# PG01_BLE_Module.net
KiCad netlist of a schematic drawn in Altium Designer
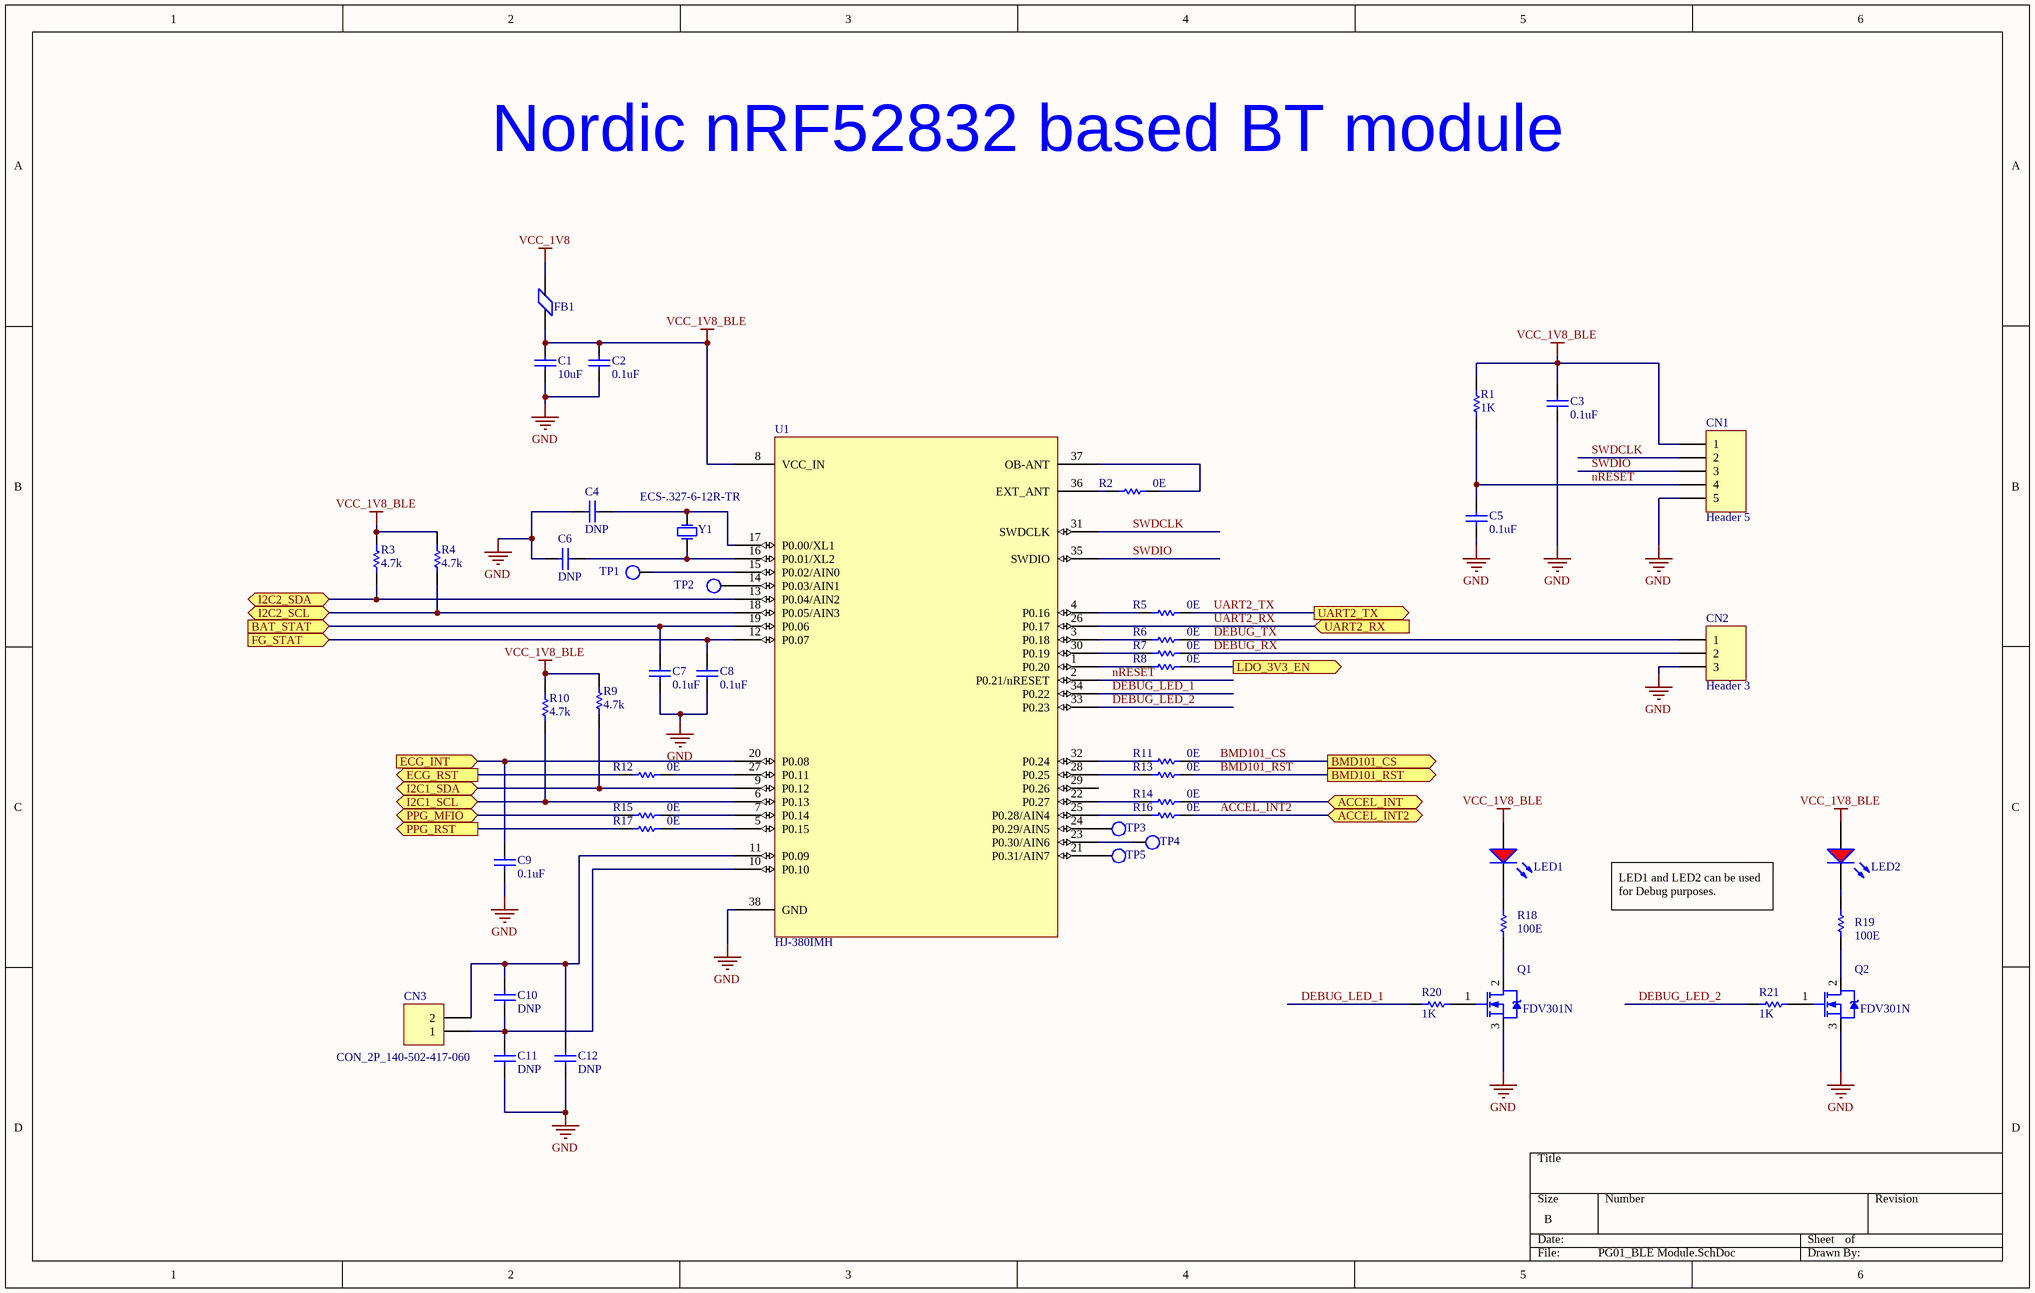
[diagram p0: PG01_BLE Module.SchDoc]

(export (version "E")
  (design (tool "Eeschema 10.0.6"))
  (components
    (comp (ref "C1")
      (value "10uF")
      (footprint "0805C")
      (description "CAP CER 10UF 16V X7R 0805")
      (libsource (lib "Smart Ring Components") (part "CAP_0805_10uF_16V"))
    )
    (comp (ref "C2")
      (value "0.1uF")
      (footprint "0402C")
      (description "CAP CER 0.1UF 50V X7R 0402")
      (libsource (lib "Smart Ring Components") (part "CAP_0402_0.1uF_50V"))
    )
    (comp (ref "C3")
      (value "0.1uF")
      (footprint "0402C")
      (description "CAP CER 0.1UF 50V X7R 0402")
      (libsource (lib "Smart Ring Components") (part "CAP_0402_0.1uF_50V"))
    )
    (comp (ref "C4")
      (value "DNP")
      (footprint "0402C")
      (description "CAP CER DNP 0402")
      (fields (field (name "MFR") "Generic"))
      (libsource (lib "Smart Ring Components") (part "CAP_0402_DNP"))
    )
    (comp (ref "C5")
      (value "0.1uF")
      (footprint "0402C")
      (description "CAP CER 0.1UF 50V X7R 0402")
      (libsource (lib "Smart Ring Components") (part "CAP_0402_0.1uF_50V"))
    )
    (comp (ref "C6")
      (value "DNP")
      (footprint "0402C")
      (description "CAP CER DNP 0402")
      (fields (field (name "MFR") "Generic"))
      (libsource (lib "Smart Ring Components") (part "CAP_0402_DNP"))
    )
    (comp (ref "C7")
      (value "0.1uF")
      (footprint "0402C")
      (description "CAP CER 0.1UF 50V X7R 0402")
      (libsource (lib "Smart Ring Components") (part "CAP_0402_0.1uF_50V"))
    )
    (comp (ref "C8")
      (value "0.1uF")
      (footprint "0402C")
      (description "CAP CER 0.1UF 50V X7R 0402")
      (libsource (lib "Smart Ring Components") (part "CAP_0402_0.1uF_50V"))
    )
    (comp (ref "C9")
      (value "0.1uF")
      (footprint "0402C")
      (description "CAP CER 0.1UF 50V X7R 0402")
      (libsource (lib "Smart Ring Components") (part "CAP_0402_0.1uF_50V"))
    )
    (comp (ref "C10")
      (value "DNP")
      (footprint "0402C")
      (description "CAP CER DNP 0402")
      (fields (field (name "MFR") "Generic"))
      (libsource (lib "Smart Ring Components") (part "CAP_0402_DNP"))
    )
    (comp (ref "C11")
      (value "DNP")
      (footprint "0402C")
      (description "CAP CER DNP 0402")
      (fields (field (name "MFR") "Generic"))
      (libsource (lib "Smart Ring Components") (part "CAP_0402_DNP"))
    )
    (comp (ref "C12")
      (value "DNP")
      (footprint "0402C")
      (description "CAP CER DNP 0402")
      (fields (field (name "MFR") "Generic"))
      (libsource (lib "Smart Ring Components") (part "CAP_0402_DNP"))
    )
    (comp (ref "CN1")
      (value "Header 5")
      (footprint "HDR1X5")
      (description "5 POS 2.00MM(.079) SINGLE ROW SM")
      (fields (field (name "MFR") "Cvilux USA") (field (name "MPN") "CI0105M1HR0-NH"))
      (libsource (lib "Smart Ring Components") (part "CON_5P_CI0105M1HR0-NH"))
    )
    (comp (ref "CN2")
      (value "Header 3")
      (footprint "HDR1X3")
      (description "3 POS 2.00MM(.079) SINGLE ROW SM")
      (fields (field (name "MFR") "Cvilux USA") (field (name "MPN") "CI0103M1HR0-NH"))
      (libsource (lib "Smart Ring Components") (part "CON_3P_CI0103M1HR0-NH"))
    )
    (comp (ref "CN3")
      (value "CON_2P_140-502-417-060")
      (footprint "140-502-417-060")
      (description "2.0MM PITCH CONNECTOR WITH 2 SUR")
      (fields (field (name "MFR") "EDAC Inc.") (field (name "MPN") "140-502-417-060"))
      (libsource (lib "Smart Ring Components") (part "CON_2P_140-502-417-060"))
    )
    (comp (ref "FB1")
      (value "Ferrite Bead")
      (footprint "0402R")
      (description "CHIP BEAD 600 OHM 0402 300mA")
      (fields (field (name "MFR") "Walsin") (field (name "MPN") "WLBD1005K2U601TP"))
      (libsource (lib "Smart Ring Components") (part "Ferrite Bead"))
    )
    (comp (ref "LED1")
      (value "5988A10107F")
      (footprint "0402R")
      (description "Red LED")
      (fields (field (name "MFR") "Dialight"))
      (libsource (lib "Smart Ring Components") (part "LED_Red"))
    )
    (comp (ref "LED2")
      (value "5988A10107F")
      (footprint "0402R")
      (description "Red LED")
      (fields (field (name "MFR") "Dialight"))
      (libsource (lib "Smart Ring Components") (part "LED_Red"))
    )
    (comp (ref "Q1")
      (value "FDV301N")
      (footprint "SOT_23")
      (description "MOSFET N-CH 25V 220MA SOT23")
      (fields (field (name "MFR") "onsemi"))
      (libsource (lib "Smart Ring Components") (part "NMOS_FDV301N"))
    )
    (comp (ref "Q2")
      (value "FDV301N")
      (footprint "SOT_23")
      (description "MOSFET N-CH 25V 220MA SOT23")
      (fields (field (name "MFR") "onsemi"))
      (libsource (lib "Smart Ring Components") (part "NMOS_FDV301N"))
    )
    (comp (ref "R1")
      (value "1K")
      (footprint "0402R")
      (description "RES SMD 1K OHM 1% 1/16W 0402")
      (fields (field (name "MFR") "Generic"))
      (libsource (lib "Smart Ring Components") (part "RES_0402_1k"))
    )
    (comp (ref "R2")
      (value "0E")
      (footprint "0402R")
      (description "RES 0 OHM JUMPER 1/16W 0402")
      (fields (field (name "MFR") "Generic"))
      (libsource (lib "Smart Ring Components") (part "RES_0402_0E"))
    )
    (comp (ref "R3")
      (value "4.7k")
      (footprint "0402R")
      (description "RES 4.7K OHM 1% 1/16W 0402")
      (fields (field (name "MFR") "Generic"))
      (libsource (lib "Smart Ring Components") (part "RES_0402_4.7k"))
    )
    (comp (ref "R4")
      (value "4.7k")
      (footprint "0402R")
      (description "RES 4.7K OHM 1% 1/16W 0402")
      (fields (field (name "MFR") "Generic"))
      (libsource (lib "Smart Ring Components") (part "RES_0402_4.7k"))
    )
    (comp (ref "R5")
      (value "0E")
      (footprint "0402R")
      (description "RES 0 OHM JUMPER 1/16W 0402")
      (fields (field (name "MFR") "Generic"))
      (libsource (lib "Smart Ring Components") (part "RES_0402_0E"))
    )
    (comp (ref "R6")
      (value "0E")
      (footprint "0402R")
      (description "RES 0 OHM JUMPER 1/16W 0402")
      (fields (field (name "MFR") "Generic"))
      (libsource (lib "Smart Ring Components") (part "RES_0402_0E"))
    )
    (comp (ref "R7")
      (value "0E")
      (footprint "0402R")
      (description "RES 0 OHM JUMPER 1/16W 0402")
      (fields (field (name "MFR") "Generic"))
      (libsource (lib "Smart Ring Components") (part "RES_0402_0E"))
    )
    (comp (ref "R8")
      (value "0E")
      (footprint "0402R")
      (description "RES 0 OHM JUMPER 1/16W 0402")
      (fields (field (name "MFR") "Generic"))
      (libsource (lib "Smart Ring Components") (part "RES_0402_0E"))
    )
    (comp (ref "R9")
      (value "4.7k")
      (footprint "0402R")
      (description "RES 4.7K OHM 1% 1/16W 0402")
      (fields (field (name "MFR") "Generic"))
      (libsource (lib "Smart Ring Components") (part "RES_0402_4.7k"))
    )
    (comp (ref "R10")
      (value "4.7k")
      (footprint "0402R")
      (description "RES 4.7K OHM 1% 1/16W 0402")
      (fields (field (name "MFR") "Generic"))
      (libsource (lib "Smart Ring Components") (part "RES_0402_4.7k"))
    )
    (comp (ref "R11")
      (value "0E")
      (footprint "0402R")
      (description "RES 0 OHM JUMPER 1/16W 0402")
      (fields (field (name "MFR") "Generic"))
      (libsource (lib "Smart Ring Components") (part "RES_0402_0E"))
    )
    (comp (ref "R12")
      (value "0E")
      (footprint "0402R")
      (description "RES 0 OHM JUMPER 1/16W 0402")
      (fields (field (name "MFR") "Generic"))
      (libsource (lib "Smart Ring Components") (part "RES_0402_0E"))
    )
    (comp (ref "R13")
      (value "0E")
      (footprint "0402R")
      (description "RES 0 OHM JUMPER 1/16W 0402")
      (fields (field (name "MFR") "Generic"))
      (libsource (lib "Smart Ring Components") (part "RES_0402_0E"))
    )
    (comp (ref "R14")
      (value "0E")
      (footprint "0402R")
      (description "RES 0 OHM JUMPER 1/16W 0402")
      (fields (field (name "MFR") "Generic"))
      (libsource (lib "Smart Ring Components") (part "RES_0402_0E"))
    )
    (comp (ref "R15")
      (value "0E")
      (footprint "0402R")
      (description "RES 0 OHM JUMPER 1/16W 0402")
      (fields (field (name "MFR") "Generic"))
      (libsource (lib "Smart Ring Components") (part "RES_0402_0E"))
    )
    (comp (ref "R16")
      (value "0E")
      (footprint "0402R")
      (description "RES 0 OHM JUMPER 1/16W 0402")
      (fields (field (name "MFR") "Generic"))
      (libsource (lib "Smart Ring Components") (part "RES_0402_0E"))
    )
    (comp (ref "R17")
      (value "0E")
      (footprint "0402R")
      (description "RES 0 OHM JUMPER 1/16W 0402")
      (fields (field (name "MFR") "Generic"))
      (libsource (lib "Smart Ring Components") (part "RES_0402_0E"))
    )
    (comp (ref "R18")
      (value "100E")
      (footprint "0402R")
      (description "RES 100 OHM 1% 1/16W 0402")
      (fields (field (name "MFR") "Generic"))
      (libsource (lib "Smart Ring Components") (part "RES_0402_100E"))
    )
    (comp (ref "R19")
      (value "100E")
      (footprint "0402R")
      (description "RES 100 OHM 1% 1/16W 0402")
      (fields (field (name "MFR") "Generic"))
      (libsource (lib "Smart Ring Components") (part "RES_0402_100E"))
    )
    (comp (ref "R20")
      (value "1K")
      (footprint "0402R")
      (description "RES SMD 1K OHM 1% 1/16W 0402")
      (fields (field (name "MFR") "Generic"))
      (libsource (lib "Smart Ring Components") (part "RES_0402_1k"))
    )
    (comp (ref "R21")
      (value "1K")
      (footprint "0402R")
      (description "RES SMD 1K OHM 1% 1/16W 0402")
      (fields (field (name "MFR") "Generic"))
      (libsource (lib "Smart Ring Components") (part "RES_0402_1k"))
    )
    (comp (ref "TP1")
      (value "Test_Point")
      (footprint "TP")
      (libsource (lib "Smart Ring Components") (part "Test_Point"))
    )
    (comp (ref "TP2")
      (value "Test_Point")
      (footprint "TP")
      (libsource (lib "Smart Ring Components") (part "Test_Point"))
    )
    (comp (ref "TP3")
      (value "Test_Point")
      (footprint "TP")
      (libsource (lib "Smart Ring Components") (part "Test_Point"))
    )
    (comp (ref "TP4")
      (value "Test_Point")
      (footprint "TP")
      (libsource (lib "Smart Ring Components") (part "Test_Point"))
    )
    (comp (ref "TP5")
      (value "Test_Point")
      (footprint "TP")
      (libsource (lib "Smart Ring Components") (part "Test_Point"))
    )
    (comp (ref "U1")
      (value "HJ-380IMH")
      (footprint "HJ-380IMH")
      (fields (field (name "MFR") "TangShan HongJia Electronic Technology Co., Ltd"))
      (libsource (lib "Smart Ring Components") (part "BLE Module_HJ-380IMH"))
    )
    (comp (ref "Y1")
      (value "ECS-.327-6-12R-TR")
      (footprint "ECS-.327-6-12R-TR")
      (description "CRYSTAL 32.7680KHZ 6PF SMD")
      (fields (field (name "MFR") "ECS Inc."))
      (libsource (lib "Smart Ring Components") (part "XTAL_32.768kHz"))
    )
  )
  (nets
    (net (code "1") (name "/ACCEL_INT") (class "Default")
      (node (ref "R14") (pin "2") (pinfunction "2_2") (pintype "passive"))
    )
    (net (code "2") (name "/ACCEL_INT2") (class "Default")
      (node (ref "R16") (pin "2") (pinfunction "2_2") (pintype "passive"))
    )
    (net (code "3") (name "/BAT_STAT") (class "Default")
      (node (ref "C7") (pin "2") (pinfunction "2_2") (pintype "passive"))
      (node (ref "U1") (pin "19") (pinfunction "P0.06_19") (pintype "bidirectional"))
    )
    (net (code "4") (name "/BMD101_CS") (class "Default")
      (node (ref "R11") (pin "2") (pinfunction "2_2") (pintype "passive"))
    )
    (net (code "5") (name "/BMD101_RST") (class "Default")
      (node (ref "R13") (pin "2") (pinfunction "2_2") (pintype "passive"))
    )
    (net (code "6") (name "/DEBUG_LED_1") (class "Default")
      (node (ref "R20") (pin "1") (pinfunction "1_1") (pintype "passive"))
      (node (ref "U1") (pin "34") (pinfunction "P0.22_34") (pintype "bidirectional"))
    )
    (net (code "7") (name "/DEBUG_LED_2") (class "Default")
      (node (ref "R21") (pin "1") (pinfunction "1_1") (pintype "passive"))
      (node (ref "U1") (pin "33") (pinfunction "P0.23_33") (pintype "bidirectional"))
    )
    (net (code "8") (name "/DEBUG_RX") (class "Default")
      (node (ref "CN2") (pin "2") (pinfunction "2_2") (pintype "passive"))
      (node (ref "R7") (pin "2") (pinfunction "2_2") (pintype "passive"))
    )
    (net (code "9") (name "/DEBUG_TX") (class "Default")
      (node (ref "CN2") (pin "1") (pinfunction "1_1") (pintype "passive"))
      (node (ref "R6") (pin "2") (pinfunction "2_2") (pintype "passive"))
    )
    (net (code "10") (name "/ECG_INT") (class "Default")
      (node (ref "C9") (pin "2") (pinfunction "2_2") (pintype "passive"))
      (node (ref "U1") (pin "20") (pinfunction "P0.08_20") (pintype "bidirectional"))
    )
    (net (code "11") (name "/ECG_RST") (class "Default")
      (node (ref "R12") (pin "1") (pinfunction "1_1") (pintype "passive"))
    )
    (net (code "12") (name "/FG_STAT") (class "Default")
      (node (ref "C8") (pin "2") (pinfunction "2_2") (pintype "passive"))
      (node (ref "U1") (pin "12") (pinfunction "P0.07_12") (pintype "bidirectional"))
    )
    (net (code "13") (name "/I2C1_SCL") (class "Default")
      (node (ref "R10") (pin "1") (pinfunction "1_1") (pintype "passive"))
      (node (ref "U1") (pin "6") (pinfunction "P0.13_6") (pintype "bidirectional"))
    )
    (net (code "14") (name "/I2C1_SDA") (class "Default")
      (node (ref "R9") (pin "1") (pinfunction "1_1") (pintype "passive"))
      (node (ref "U1") (pin "9") (pinfunction "P0.12_9") (pintype "bidirectional"))
    )
    (net (code "15") (name "/I2C2_SCL") (class "Default")
      (node (ref "R4") (pin "1") (pinfunction "1_1") (pintype "passive"))
      (node (ref "U1") (pin "18") (pinfunction "P0.05/AIN3_18") (pintype "bidirectional"))
    )
    (net (code "16") (name "/I2C2_SDA") (class "Default")
      (node (ref "R3") (pin "1") (pinfunction "1_1") (pintype "passive"))
      (node (ref "U1") (pin "13") (pinfunction "P0.04/AIN2_13") (pintype "bidirectional"))
    )
    (net (code "17") (name "/LDO_3V3_EN") (class "Default")
      (node (ref "R8") (pin "2") (pinfunction "2_2") (pintype "passive"))
    )
    (net (code "18") (name "/PPG_MFIO") (class "Default")
      (node (ref "R15") (pin "1") (pinfunction "1_1") (pintype "passive"))
    )
    (net (code "19") (name "/PPG_RST") (class "Default")
      (node (ref "R17") (pin "1") (pinfunction "1_1") (pintype "passive"))
    )
    (net (code "20") (name "/SWDCLK") (class "Default")
      (node (ref "CN1") (pin "2") (pinfunction "2_2") (pintype "passive"))
      (node (ref "U1") (pin "31") (pinfunction "SWDCLK_31") (pintype "bidirectional"))
    )
    (net (code "21") (name "/SWDIO") (class "Default")
      (node (ref "CN1") (pin "3") (pinfunction "3_3") (pintype "passive"))
      (node (ref "U1") (pin "35") (pinfunction "SWDIO_35") (pintype "bidirectional"))
    )
    (net (code "22") (name "/UART2_RX") (class "Default")
      (node (ref "U1") (pin "26") (pinfunction "P0.17_26") (pintype "bidirectional"))
    )
    (net (code "23") (name "/UART2_TX") (class "Default")
      (node (ref "R5") (pin "2") (pinfunction "2_2") (pintype "passive"))
    )
    (net (code "24") (name "/nRESET") (class "Default")
      (node (ref "C5") (pin "1") (pinfunction "1_1") (pintype "passive"))
      (node (ref "CN1") (pin "4") (pinfunction "4_4") (pintype "passive"))
      (node (ref "R1") (pin "1") (pinfunction "1_1") (pintype "passive"))
      (node (ref "U1") (pin "2") (pinfunction "P0.21/nRESET_2") (pintype "bidirectional"))
    )
    (net (code "25") (name "GND") (class "Default")
      (node (ref "C1") (pin "1") (pinfunction "1_1") (pintype "passive"))
      (node (ref "C11") (pin "1") (pinfunction "1_1") (pintype "passive"))
      (node (ref "C12") (pin "1") (pinfunction "1_1") (pintype "passive"))
      (node (ref "C2") (pin "1") (pinfunction "1_1") (pintype "passive"))
      (node (ref "C3") (pin "2") (pinfunction "2_2") (pintype "passive"))
      (node (ref "C4") (pin "2") (pinfunction "2_2") (pintype "passive"))
      (node (ref "C5") (pin "2") (pinfunction "2_2") (pintype "passive"))
      (node (ref "C6") (pin "2") (pinfunction "2_2") (pintype "passive"))
      (node (ref "C7") (pin "1") (pinfunction "1_1") (pintype "passive"))
      (node (ref "C8") (pin "1") (pinfunction "1_1") (pintype "passive"))
      (node (ref "C9") (pin "1") (pinfunction "1_1") (pintype "passive"))
      (node (ref "CN1") (pin "5") (pinfunction "5_5") (pintype "passive"))
      (node (ref "CN2") (pin "3") (pinfunction "3_3") (pintype "passive"))
      (node (ref "Q1") (pin "3") (pinfunction "S_3") (pintype "passive"))
      (node (ref "Q2") (pin "3") (pinfunction "S_3") (pintype "passive"))
      (node (ref "U1") (pin "38") (pinfunction "GND_38") (pintype "power_in"))
    )
    (net (code "26") (name "Net-(LED1-K)") (class "Default")
      (node (ref "LED1") (pin "2") (pinfunction "K_2") (pintype "passive"))
      (node (ref "R18") (pin "2") (pinfunction "2_2") (pintype "passive"))
    )
    (net (code "27") (name "Net-(LED2-K)") (class "Default")
      (node (ref "LED2") (pin "2") (pinfunction "K_2") (pintype "passive"))
      (node (ref "R19") (pin "2") (pinfunction "2_2") (pintype "passive"))
    )
    (net (code "28") (name "Net-(Q1-D)") (class "Default")
      (node (ref "Q1") (pin "2") (pinfunction "D_2") (pintype "passive"))
      (node (ref "R18") (pin "1") (pinfunction "1_1") (pintype "passive"))
    )
    (net (code "29") (name "Net-(Q1-G)") (class "Default")
      (node (ref "Q1") (pin "1") (pinfunction "G_1") (pintype "passive"))
      (node (ref "R20") (pin "2") (pinfunction "2_2") (pintype "passive"))
    )
    (net (code "30") (name "Net-(Q2-D)") (class "Default")
      (node (ref "Q2") (pin "2") (pinfunction "D_2") (pintype "passive"))
      (node (ref "R19") (pin "1") (pinfunction "1_1") (pintype "passive"))
    )
    (net (code "31") (name "Net-(Q2-G)") (class "Default")
      (node (ref "Q2") (pin "1") (pinfunction "G_1") (pintype "passive"))
      (node (ref "R21") (pin "2") (pinfunction "2_2") (pintype "passive"))
    )
    (net (code "32") (name "Net-(U1-EXT_ANT)") (class "Default")
      (node (ref "R2") (pin "1") (pinfunction "1_1") (pintype "passive"))
      (node (ref "U1") (pin "36") (pinfunction "EXT_ANT_36") (pintype "passive"))
    )
    (net (code "33") (name "Net-(U1-OB-ANT)") (class "Default")
      (node (ref "R2") (pin "2") (pinfunction "2_2") (pintype "passive"))
      (node (ref "U1") (pin "37") (pinfunction "OB-ANT_37") (pintype "passive"))
    )
    (net (code "34") (name "Net-(U1-P0.00{slash}XL1)") (class "Default")
      (node (ref "C4") (pin "1") (pinfunction "1_1") (pintype "passive"))
      (node (ref "U1") (pin "17") (pinfunction "P0.00/XL1_17") (pintype "bidirectional"))
      (node (ref "Y1") (pin "2") (pinfunction "OSC2_2") (pintype "passive"))
    )
    (net (code "35") (name "Net-(U1-P0.01{slash}XL2)") (class "Default")
      (node (ref "C6") (pin "1") (pinfunction "1_1") (pintype "passive"))
      (node (ref "U1") (pin "16") (pinfunction "P0.01/XL2_16") (pintype "bidirectional"))
      (node (ref "Y1") (pin "1") (pinfunction "OSC1_1") (pintype "passive"))
    )
    (net (code "36") (name "Net-(U1-P0.02{slash}AIN0)") (class "Default")
      (node (ref "TP1") (pin "1") (pintype "passive"))
      (node (ref "U1") (pin "15") (pinfunction "P0.02/AIN0_15") (pintype "bidirectional"))
    )
    (net (code "37") (name "Net-(U1-P0.03{slash}AIN1)") (class "Default")
      (node (ref "TP2") (pin "1") (pintype "passive"))
      (node (ref "U1") (pin "14") (pinfunction "P0.03/AIN1_14") (pintype "bidirectional"))
    )
    (net (code "38") (name "Net-(U1-P0.09)") (class "Default")
      (node (ref "C10") (pin "2") (pinfunction "2_2") (pintype "passive"))
      (node (ref "C12") (pin "2") (pinfunction "2_2") (pintype "passive"))
      (node (ref "CN3") (pin "2") (pinfunction "2_2") (pintype "passive"))
      (node (ref "U1") (pin "11") (pinfunction "P0.09_11") (pintype "bidirectional"))
    )
    (net (code "39") (name "Net-(U1-P0.10)") (class "Default")
      (node (ref "C10") (pin "1") (pinfunction "1_1") (pintype "passive"))
      (node (ref "C11") (pin "2") (pinfunction "2_2") (pintype "passive"))
      (node (ref "CN3") (pin "1") (pinfunction "1_1") (pintype "passive"))
      (node (ref "U1") (pin "10") (pinfunction "P0.10_10") (pintype "bidirectional"))
    )
    (net (code "40") (name "Net-(U1-P0.11)") (class "Default")
      (node (ref "R12") (pin "2") (pinfunction "2_2") (pintype "passive"))
      (node (ref "U1") (pin "27") (pinfunction "P0.11_27") (pintype "bidirectional"))
    )
    (net (code "41") (name "Net-(U1-P0.14)") (class "Default")
      (node (ref "R15") (pin "2") (pinfunction "2_2") (pintype "passive"))
      (node (ref "U1") (pin "7") (pinfunction "P0.14_7") (pintype "bidirectional"))
    )
    (net (code "42") (name "Net-(U1-P0.15)") (class "Default")
      (node (ref "R17") (pin "2") (pinfunction "2_2") (pintype "passive"))
      (node (ref "U1") (pin "5") (pinfunction "P0.15_5") (pintype "bidirectional"))
    )
    (net (code "43") (name "Net-(U1-P0.16)") (class "Default")
      (node (ref "R5") (pin "1") (pinfunction "1_1") (pintype "passive"))
      (node (ref "U1") (pin "4") (pinfunction "P0.16_4") (pintype "bidirectional"))
    )
    (net (code "44") (name "Net-(U1-P0.18)") (class "Default")
      (node (ref "R6") (pin "1") (pinfunction "1_1") (pintype "passive"))
      (node (ref "U1") (pin "3") (pinfunction "P0.18_3") (pintype "bidirectional"))
    )
    (net (code "45") (name "Net-(U1-P0.19)") (class "Default")
      (node (ref "R7") (pin "1") (pinfunction "1_1") (pintype "passive"))
      (node (ref "U1") (pin "30") (pinfunction "P0.19_30") (pintype "bidirectional"))
    )
    (net (code "46") (name "Net-(U1-P0.20)") (class "Default")
      (node (ref "R8") (pin "1") (pinfunction "1_1") (pintype "passive"))
      (node (ref "U1") (pin "1") (pinfunction "P0.20_1") (pintype "bidirectional"))
    )
    (net (code "47") (name "Net-(U1-P0.24)") (class "Default")
      (node (ref "R11") (pin "1") (pinfunction "1_1") (pintype "passive"))
      (node (ref "U1") (pin "32") (pinfunction "P0.24_32") (pintype "bidirectional"))
    )
    (net (code "48") (name "Net-(U1-P0.25)") (class "Default")
      (node (ref "R13") (pin "1") (pinfunction "1_1") (pintype "passive"))
      (node (ref "U1") (pin "28") (pinfunction "P0.25_28") (pintype "bidirectional"))
    )
    (net (code "49") (name "Net-(U1-P0.27)") (class "Default")
      (node (ref "R14") (pin "1") (pinfunction "1_1") (pintype "passive"))
      (node (ref "U1") (pin "22") (pinfunction "P0.27_22") (pintype "bidirectional"))
    )
    (net (code "50") (name "Net-(U1-P0.28{slash}AIN4)") (class "Default")
      (node (ref "R16") (pin "1") (pinfunction "1_1") (pintype "passive"))
      (node (ref "U1") (pin "25") (pinfunction "P0.28/AIN4_25") (pintype "bidirectional"))
    )
    (net (code "51") (name "Net-(U1-P0.29{slash}AIN5)") (class "Default")
      (node (ref "TP3") (pin "1") (pintype "passive"))
      (node (ref "U1") (pin "24") (pinfunction "P0.29/AIN5_24") (pintype "bidirectional"))
    )
    (net (code "52") (name "Net-(U1-P0.30{slash}AIN6)") (class "Default")
      (node (ref "TP4") (pin "1") (pintype "passive"))
      (node (ref "U1") (pin "23") (pinfunction "P0.30/AIN6_23") (pintype "bidirectional"))
    )
    (net (code "53") (name "Net-(U1-P0.31{slash}AIN7)") (class "Default")
      (node (ref "TP5") (pin "1") (pintype "passive"))
      (node (ref "U1") (pin "21") (pinfunction "P0.31/AIN7_21") (pintype "bidirectional"))
    )
    (net (code "54") (name "VCC_1V8") (class "Default")
      (node (ref "FB1") (pin "2") (pinfunction "VREF_2") (pintype "passive"))
    )
    (net (code "55") (name "VCC_1V8_BLE") (class "Default")
      (node (ref "C1") (pin "2") (pinfunction "2_2") (pintype "passive"))
      (node (ref "C2") (pin "2") (pinfunction "2_2") (pintype "passive"))
      (node (ref "C3") (pin "1") (pinfunction "1_1") (pintype "passive"))
      (node (ref "CN1") (pin "1") (pinfunction "1_1") (pintype "passive"))
      (node (ref "FB1") (pin "1") (pinfunction "VREF_1") (pintype "passive"))
      (node (ref "LED1") (pin "1") (pinfunction "A_1") (pintype "passive"))
      (node (ref "LED2") (pin "1") (pinfunction "A_1") (pintype "passive"))
      (node (ref "R1") (pin "2") (pinfunction "2_2") (pintype "passive"))
      (node (ref "R10") (pin "2") (pinfunction "2_2") (pintype "passive"))
      (node (ref "R3") (pin "2") (pinfunction "2_2") (pintype "passive"))
      (node (ref "R4") (pin "2") (pinfunction "2_2") (pintype "passive"))
      (node (ref "R9") (pin "2") (pinfunction "2_2") (pintype "passive"))
      (node (ref "U1") (pin "8") (pinfunction "VCC_IN_8") (pintype "power_in"))
    )
    (net (code "56") (name "unconnected-(U1-P0.26-Pad29)") (class "Default")
      (node (ref "U1") (pin "29") (pinfunction "P0.26_29") (pintype "bidirectional"))
    )
  )
)
